# RaspShield.net
KiCad netlist of a schematic drawn in EAGLE
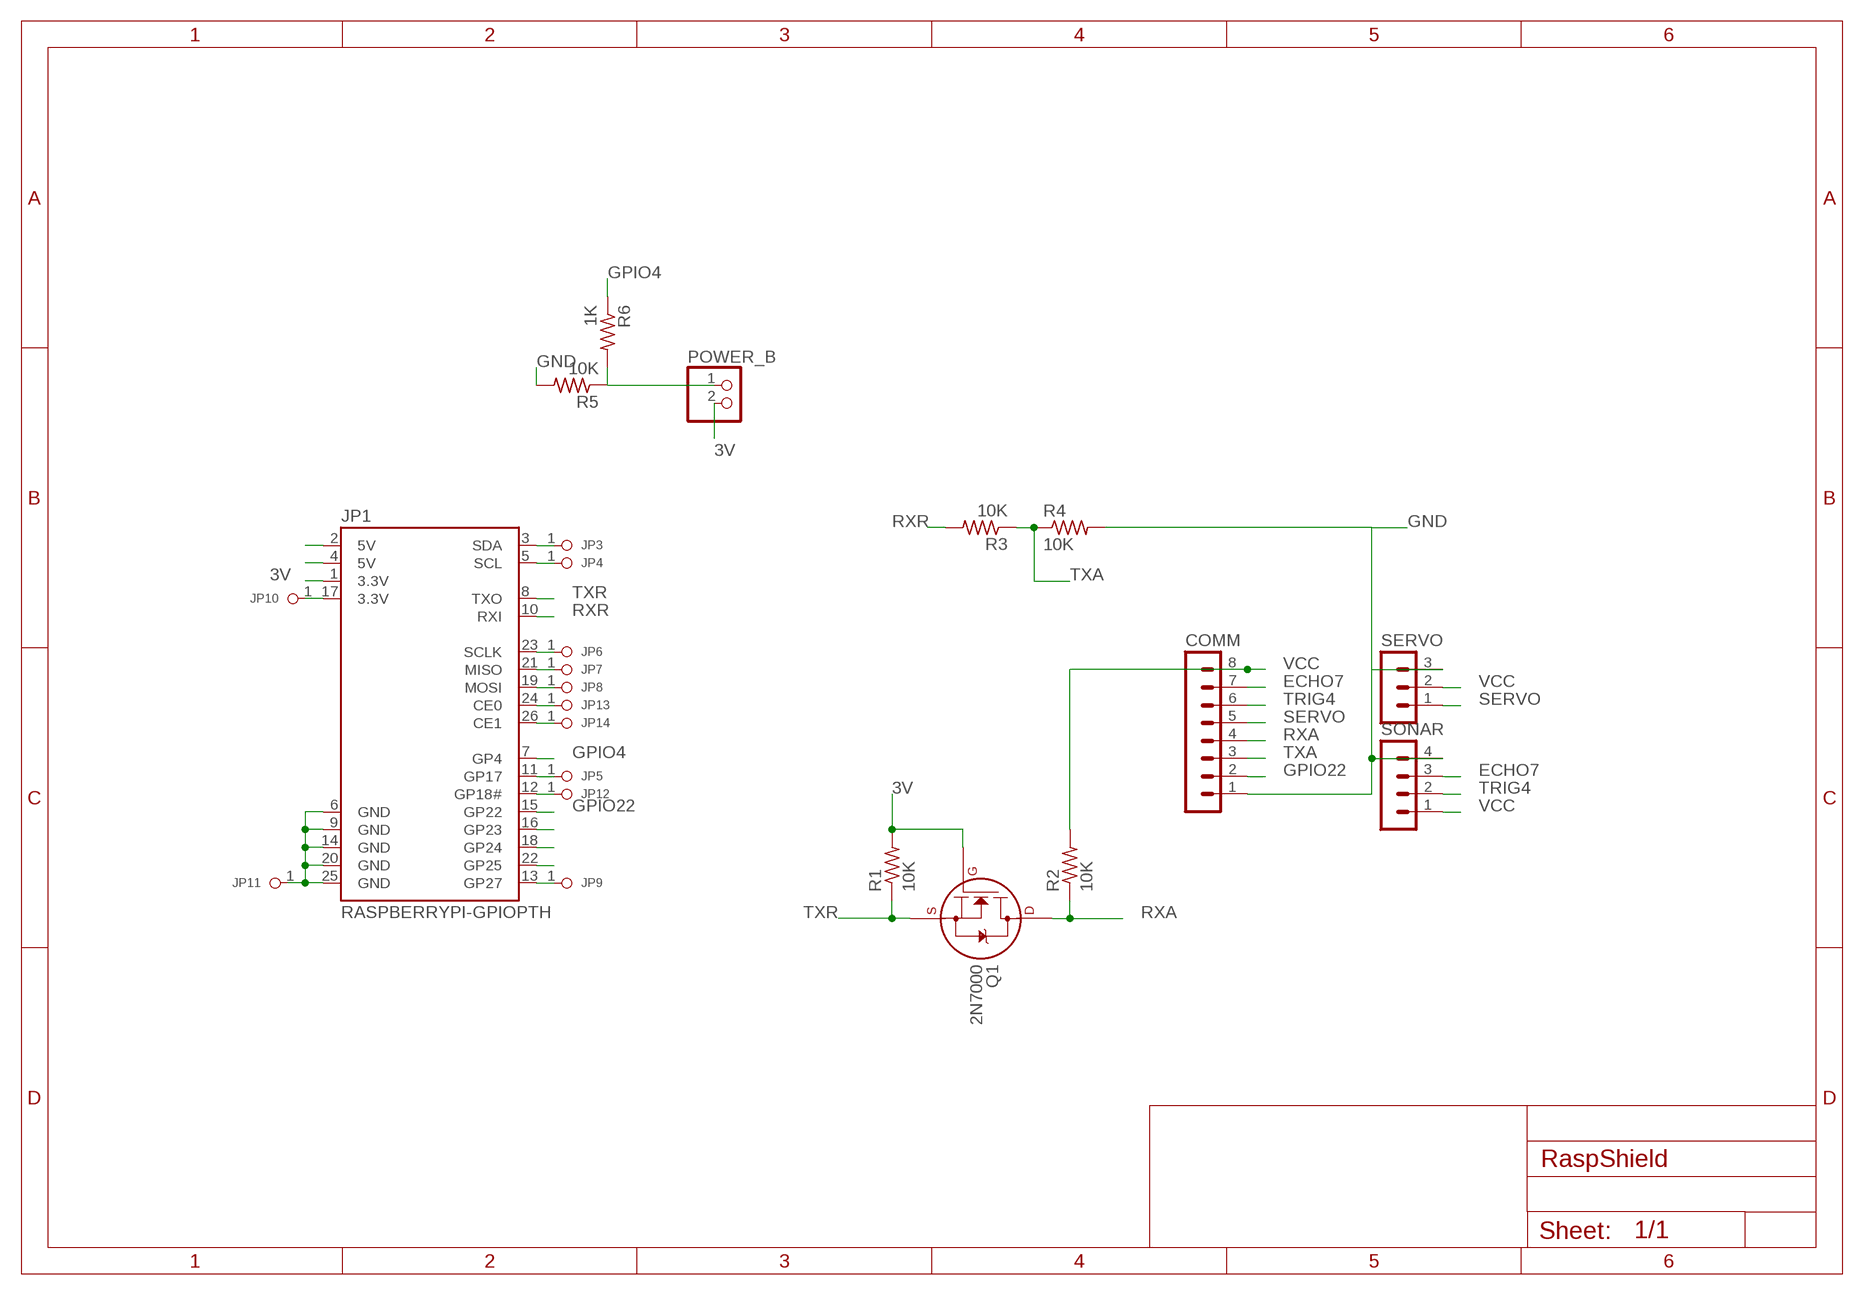
[diagram p0: schematic, sheet 1]

(export (version "E")
  (design (tool "Eeschema 10.0.6"))
  (components
    (comp (ref "COMM")
      (value "MA08-1")
      (footprint "eagle-import:MA08-1")
      (libsource (lib "eagle-import") (part "MA08-1"))
    )
    (comp (ref "JP1")
      (value "RASPBERRYPI-GPIOPTH")
      (footprint "eagle-import:2X13-SHROUDED")
      (libsource (lib "eagle-import") (part "RASPBERRYPI-GPIOPTH"))
    )
    (comp (ref "JP3")
      (value "PINHD-1X1")
      (footprint "eagle-import:1X01")
      (libsource (lib "eagle-import") (part "PINHD-1X1"))
    )
    (comp (ref "JP4")
      (value "PINHD-1X1")
      (footprint "eagle-import:1X01")
      (libsource (lib "eagle-import") (part "PINHD-1X1"))
    )
    (comp (ref "JP5")
      (value "PINHD-1X1")
      (footprint "eagle-import:1X01")
      (libsource (lib "eagle-import") (part "PINHD-1X1"))
    )
    (comp (ref "JP6")
      (value "PINHD-1X1")
      (footprint "eagle-import:1X01")
      (libsource (lib "eagle-import") (part "PINHD-1X1"))
    )
    (comp (ref "JP7")
      (value "PINHD-1X1")
      (footprint "eagle-import:1X01")
      (libsource (lib "eagle-import") (part "PINHD-1X1"))
    )
    (comp (ref "JP8")
      (value "PINHD-1X1")
      (footprint "eagle-import:1X01")
      (libsource (lib "eagle-import") (part "PINHD-1X1"))
    )
    (comp (ref "JP9")
      (value "PINHD-1X1")
      (footprint "eagle-import:1X01")
      (libsource (lib "eagle-import") (part "PINHD-1X1"))
    )
    (comp (ref "JP10")
      (value "PINHD-1X1")
      (footprint "eagle-import:1X01")
      (libsource (lib "eagle-import") (part "PINHD-1X1"))
    )
    (comp (ref "JP11")
      (value "PINHD-1X1")
      (footprint "eagle-import:1X01")
      (libsource (lib "eagle-import") (part "PINHD-1X1"))
    )
    (comp (ref "JP12")
      (value "PINHD-1X1")
      (footprint "eagle-import:1X01")
      (libsource (lib "eagle-import") (part "PINHD-1X1"))
    )
    (comp (ref "JP13")
      (value "PINHD-1X1")
      (footprint "eagle-import:1X01")
      (libsource (lib "eagle-import") (part "PINHD-1X1"))
    )
    (comp (ref "JP14")
      (value "PINHD-1X1")
      (footprint "eagle-import:1X01")
      (libsource (lib "eagle-import") (part "PINHD-1X1"))
    )
    (comp (ref "POWER_B")
      (value "PINHD-1X2")
      (footprint "eagle-import:1X02")
      (libsource (lib "eagle-import") (part "PINHD-1X2"))
    )
    (comp (ref "Q1")
      (value "2N7000")
      (footprint "eagle-import:TO-92")
      (libsource (lib "eagle-import") (part "2N700_TO920"))
    )
    (comp (ref "R1")
      (value "10K")
      (footprint "eagle-import:0207_7")
      (libsource (lib "eagle-import") (part "R-US_0207/7"))
    )
    (comp (ref "R2")
      (value "10K")
      (footprint "eagle-import:0207_7")
      (libsource (lib "eagle-import") (part "R-US_0207/7"))
    )
    (comp (ref "R3")
      (value "10K")
      (footprint "eagle-import:0207_7")
      (libsource (lib "eagle-import") (part "R-US_0207/7"))
    )
    (comp (ref "R4")
      (value "10K")
      (footprint "eagle-import:0207_7")
      (libsource (lib "eagle-import") (part "R-US_0207/7"))
    )
    (comp (ref "R5")
      (value "10K")
      (footprint "eagle-import:0207_7")
      (libsource (lib "eagle-import") (part "R-US_0207/7"))
    )
    (comp (ref "R6")
      (value "1K")
      (footprint "eagle-import:0207_7")
      (libsource (lib "eagle-import") (part "R-US_0207/7"))
    )
    (comp (ref "SERVO")
      (value "MA03-1")
      (footprint "eagle-import:MA03-1")
      (libsource (lib "eagle-import") (part "MA03-1"))
    )
    (comp (ref "SONAR")
      (value "MA04-1")
      (footprint "eagle-import:MA04-1")
      (libsource (lib "eagle-import") (part "MA04-1"))
    )
  )
  (nets
    (net (code "1") (name "/3V") (class "Default")
      (node (ref "JP1") (pin "1") (pinfunction "3.3V_1") (pintype "power_in"))
      (node (ref "POWER_B") (pin "2") (pinfunction "2_2") (pintype "passive"))
      (node (ref "Q1") (pin "2") (pinfunction "G_2") (pintype "tri_state"))
      (node (ref "R1") (pin "2") (pinfunction "2_2") (pintype "passive"))
    )
    (net (code "2") (name "/ECHO7") (class "Default")
      (node (ref "COMM") (pin "7") (pinfunction "7_7") (pintype "passive"))
      (node (ref "SONAR") (pin "3") (pinfunction "3_3") (pintype "passive"))
    )
    (net (code "3") (name "/GND") (class "Default")
      (node (ref "COMM") (pin "1") (pinfunction "1_1") (pintype "passive"))
      (node (ref "R4") (pin "2") (pinfunction "2_2") (pintype "passive"))
      (node (ref "R5") (pin "2") (pinfunction "2_2") (pintype "passive"))
      (node (ref "SERVO") (pin "3") (pinfunction "3_3") (pintype "passive"))
      (node (ref "SONAR") (pin "4") (pinfunction "4_4") (pintype "passive"))
    )
    (net (code "4") (name "/GPIO4") (class "Default")
      (node (ref "JP1") (pin "7") (pinfunction "GP4_7") (pintype "bidirectional"))
      (node (ref "R6") (pin "1") (pinfunction "1_1") (pintype "passive"))
    )
    (net (code "5") (name "/GPIO22") (class "Default")
      (node (ref "COMM") (pin "2") (pinfunction "2_2") (pintype "passive"))
      (node (ref "JP1") (pin "15") (pinfunction "GP22_15") (pintype "bidirectional"))
    )
    (net (code "6") (name "/RXA") (class "Default")
      (node (ref "COMM") (pin "4") (pinfunction "4_4") (pintype "passive"))
      (node (ref "Q1") (pin "3") (pinfunction "D_3") (pintype "bidirectional"))
      (node (ref "R2") (pin "1") (pinfunction "1_1") (pintype "passive"))
    )
    (net (code "7") (name "/RXR") (class "Default")
      (node (ref "JP1") (pin "10") (pinfunction "RXI_10") (pintype "input"))
      (node (ref "R3") (pin "2") (pinfunction "2_2") (pintype "passive"))
    )
    (net (code "8") (name "/SERVO") (class "Default")
      (node (ref "COMM") (pin "5") (pinfunction "5_5") (pintype "passive"))
      (node (ref "SERVO") (pin "1") (pinfunction "1_1") (pintype "passive"))
    )
    (net (code "9") (name "/TRIG4") (class "Default")
      (node (ref "COMM") (pin "6") (pinfunction "6_6") (pintype "passive"))
      (node (ref "SONAR") (pin "2") (pinfunction "2_2") (pintype "passive"))
    )
    (net (code "10") (name "/TXA") (class "Default")
      (node (ref "COMM") (pin "3") (pinfunction "3_3") (pintype "passive"))
      (node (ref "R3") (pin "1") (pinfunction "1_1") (pintype "passive"))
      (node (ref "R4") (pin "1") (pinfunction "1_1") (pintype "passive"))
    )
    (net (code "11") (name "/TXR") (class "Default")
      (node (ref "JP1") (pin "8") (pinfunction "TXO_8") (pintype "output"))
      (node (ref "Q1") (pin "1") (pinfunction "S_1") (pintype "bidirectional"))
      (node (ref "R1") (pin "1") (pinfunction "1_1") (pintype "passive"))
    )
    (net (code "12") (name "/VCC") (class "Default")
      (node (ref "COMM") (pin "8") (pinfunction "8_8") (pintype "passive"))
      (node (ref "R2") (pin "2") (pinfunction "2_2") (pintype "passive"))
      (node (ref "SERVO") (pin "2") (pinfunction "2_2") (pintype "passive"))
      (node (ref "SONAR") (pin "1") (pinfunction "1_1") (pintype "passive"))
    )
    (net (code "13") (name "Net-(JP1-3.3V-Pad17)") (class "Default")
      (node (ref "JP1") (pin "17") (pinfunction "3.3V_17") (pintype "power_in"))
      (node (ref "JP10") (pin "1") (pinfunction "1_1") (pintype "passive"))
    )
    (net (code "14") (name "Net-(JP1-CE0)") (class "Default")
      (node (ref "JP1") (pin "24") (pinfunction "CE0_24") (pintype "output"))
      (node (ref "JP13") (pin "1") (pinfunction "1_1") (pintype "passive"))
    )
    (net (code "15") (name "Net-(JP1-CE1)") (class "Default")
      (node (ref "JP1") (pin "26") (pinfunction "CE1_26") (pintype "output"))
      (node (ref "JP14") (pin "1") (pinfunction "1_1") (pintype "passive"))
    )
    (net (code "16") (name "Net-(JP1-GND-Pad14)") (class "Default")
      (node (ref "JP1") (pin "14") (pinfunction "GND_14") (pintype "power_in"))
      (node (ref "JP1") (pin "20") (pinfunction "GND_20") (pintype "power_in"))
      (node (ref "JP1") (pin "25") (pinfunction "GND_25") (pintype "power_in"))
      (node (ref "JP1") (pin "6") (pinfunction "GND_6") (pintype "power_in"))
      (node (ref "JP1") (pin "9") (pinfunction "GND_9") (pintype "power_in"))
      (node (ref "JP11") (pin "1") (pinfunction "1_1") (pintype "passive"))
    )
    (net (code "17") (name "Net-(JP1-GP17)") (class "Default")
      (node (ref "JP1") (pin "11") (pinfunction "GP17_11") (pintype "bidirectional"))
      (node (ref "JP5") (pin "1") (pinfunction "1_1") (pintype "passive"))
    )
    (net (code "18") (name "Net-(JP1-GP18#)") (class "Default")
      (node (ref "JP1") (pin "12") (pinfunction "GP18#_12") (pintype "bidirectional"))
      (node (ref "JP12") (pin "1") (pinfunction "1_1") (pintype "passive"))
    )
    (net (code "19") (name "Net-(JP1-GP27)") (class "Default")
      (node (ref "JP1") (pin "13") (pinfunction "GP27_13") (pintype "bidirectional"))
      (node (ref "JP9") (pin "1") (pinfunction "1_1") (pintype "passive"))
    )
    (net (code "20") (name "Net-(JP1-MISO)") (class "Default")
      (node (ref "JP1") (pin "21") (pinfunction "MISO_21") (pintype "input"))
      (node (ref "JP7") (pin "1") (pinfunction "1_1") (pintype "passive"))
    )
    (net (code "21") (name "Net-(JP1-MOSI)") (class "Default")
      (node (ref "JP1") (pin "19") (pinfunction "MOSI_19") (pintype "output"))
      (node (ref "JP8") (pin "1") (pinfunction "1_1") (pintype "passive"))
    )
    (net (code "22") (name "Net-(JP1-SCL)") (class "Default")
      (node (ref "JP1") (pin "5") (pinfunction "SCL_5") (pintype "bidirectional"))
      (node (ref "JP4") (pin "1") (pinfunction "1_1") (pintype "passive"))
    )
    (net (code "23") (name "Net-(JP1-SCLK)") (class "Default")
      (node (ref "JP1") (pin "23") (pinfunction "SCLK_23") (pintype "output"))
      (node (ref "JP6") (pin "1") (pinfunction "1_1") (pintype "passive"))
    )
    (net (code "24") (name "Net-(JP1-SDA)") (class "Default")
      (node (ref "JP1") (pin "3") (pinfunction "SDA_3") (pintype "bidirectional"))
      (node (ref "JP3") (pin "1") (pinfunction "1_1") (pintype "passive"))
    )
    (net (code "25") (name "Net-(POWER_B-Pad1)") (class "Default")
      (node (ref "POWER_B") (pin "1") (pinfunction "1_1") (pintype "passive"))
      (node (ref "R5") (pin "1") (pinfunction "1_1") (pintype "passive"))
      (node (ref "R6") (pin "2") (pinfunction "2_2") (pintype "passive"))
    )
    (net (code "26") (name "unconnected-(JP1-5V-Pad2)") (class "Default")
      (node (ref "JP1") (pin "2") (pinfunction "5V_2") (pintype "power_in"))
    )
    (net (code "27") (name "unconnected-(JP1-5V-Pad4)") (class "Default")
      (node (ref "JP1") (pin "4") (pinfunction "5V_4") (pintype "power_in"))
    )
    (net (code "28") (name "unconnected-(JP1-GP23-Pad16)") (class "Default")
      (node (ref "JP1") (pin "16") (pinfunction "GP23_16") (pintype "bidirectional"))
    )
    (net (code "29") (name "unconnected-(JP1-GP24-Pad18)") (class "Default")
      (node (ref "JP1") (pin "18") (pinfunction "GP24_18") (pintype "bidirectional"))
    )
    (net (code "30") (name "unconnected-(JP1-GP25-Pad22)") (class "Default")
      (node (ref "JP1") (pin "22") (pinfunction "GP25_22") (pintype "bidirectional"))
    )
  )
)
